# CC-S09-V00-PSU-3V3.net
KiCad netlist of a schematic drawn in Altium Designer
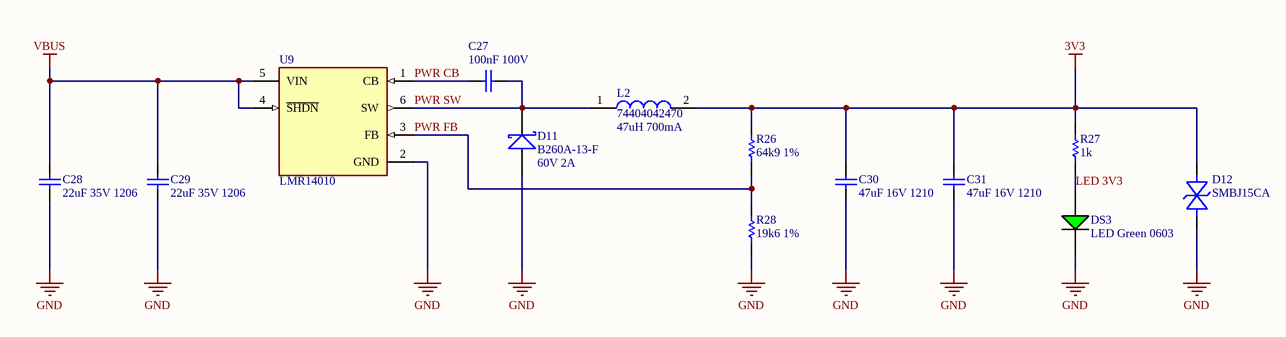
[diagram p0: CC-S09-V00-PSU-3V3.SchDoc]

(export (version "E")
  (design (tool "Eeschema 10.0.6"))
  (components
    (comp (ref "C27")
      (value "100nF 100V")
      (footprint "Cap_Ceramic_0603")
      (description "Capacitor, Ceramic, SMD, 100nF, 100V, 5%, X7R, 0603")
      (libsource (lib "StandardCapacitors") (part "100nF 100V 5% X7R 0603"))
    )
    (comp (ref "C28")
      (value "22uF 35V 1206")
      (footprint "Cap_Ceramic_1206")
      (description "Capacitor, Ceramic, SMD, 22uF, 35V, 10%, X7R, 1206")
      (libsource (lib "StandardCapacitors") (part "22uF 35V 10% X7R 1206"))
    )
    (comp (ref "C29")
      (value "22uF 35V 1206")
      (footprint "Cap_Ceramic_1206")
      (description "Capacitor, Ceramic, SMD, 22uF, 35V, 10%, X7R, 1206")
      (libsource (lib "StandardCapacitors") (part "22uF 35V 10% X7R 1206"))
    )
    (comp (ref "C30")
      (value "47uF 16V 1210")
      (footprint "Cap_Ceramic_1210")
      (description "Capacitor, Ceramic, SMD, 47uF, 16V, 5%, X7R, 1210")
      (libsource (lib "StandardCapacitors") (part "47uF 16V 10% X7R 1210"))
    )
    (comp (ref "C31")
      (value "47uF 16V 1210")
      (footprint "Cap_Ceramic_1210")
      (description "Capacitor, Ceramic, SMD, 47uF, 16V, 5%, X7R, 1210")
      (libsource (lib "StandardCapacitors") (part "47uF 16V 10% X7R 1210"))
    )
    (comp (ref "D11")
      (value "B260A-13-F")
      (footprint "SMA")
      (description "Diode, Schottky Barrier Rectifier, 60 V, 2 A, B260A-13-F")
      (libsource (lib "QUTMS_DiodeLibrary") (part "B260A-13-F"))
    )
    (comp (ref "D12")
      (value "SMBJ15CA")
      (footprint "SMB")
      (description "Diode, SMD, TVS Diode, 15V 24.4V, DO214AA/SMB")
      (libsource (lib "QUTMS_DiodeLibrary") (part "SMBJ15CA"))
    )
    (comp (ref "DS3")
      (value "LED Green 0603")
      (footprint "LED GREEN 0603")
      (libsource (lib "QUTMS_LEDLibrary") (part "LED Green 0603"))
    )
    (comp (ref "L2")
      (value "74404042470")
      (footprint "INDUCTOR_4X3MM_1.8MM")
      (description "47µH Semi-Shielded Wirewound Inductor 600mA 620mOhm Nonstandard")
      (libsource (lib "QUTMS_InductorLibrary") (part "74404042470"))
    )
    (comp (ref "R26")
      (value "64k9 1%")
      (footprint "Res_ThinFilm_0603")
      (description "Resistor, SMD, 64k9, 0.1W, 5%, 0603")
      (libsource (lib "StandardResistors") (part "64k9 1% 0603"))
    )
    (comp (ref "R27")
      (value "1k")
      (footprint "Res_ThinFilm_0603")
      (description "Resistor, SMD, 1k, 0.1W, 5%, 0603")
      (libsource (lib "StandardResistors") (part "1k 5% 0603"))
    )
    (comp (ref "R28")
      (value "19k6 1%")
      (footprint "Res_ThinFilm_0603")
      (description "Resistor, SMD, 19k6, 0.1W, 5%, 0603")
      (libsource (lib "StandardResistors") (part "19k6 1% 0603"))
    )
    (comp (ref "U9")
      (value "LMR14010")
      (footprint "LMR14010")
      (libsource (lib "QUTMS_PowerSupplyLibrary") (part "LMR14010"))
    )
  )
  (nets
    (net (code "1") (name "/LED 3V3") (class "Default")
      (node (ref "DS3") (pin "1") (pinfunction "A_1") (pintype "passive"))
      (node (ref "R27") (pin "1") (pinfunction "1_1") (pintype "passive"))
    )
    (net (code "2") (name "/PWR CB") (class "Default")
      (node (ref "C27") (pin "1") (pinfunction "1_1") (pintype "passive"))
      (node (ref "U9") (pin "1") (pinfunction "CB_1") (pintype "input"))
    )
    (net (code "3") (name "/PWR FB") (class "Default")
      (node (ref "R26") (pin "1") (pinfunction "1_1") (pintype "passive"))
      (node (ref "R28") (pin "2") (pinfunction "2_2") (pintype "passive"))
      (node (ref "U9") (pin "3") (pinfunction "FB_3") (pintype "input"))
    )
    (net (code "4") (name "/PWR SW") (class "Default")
      (node (ref "C27") (pin "2") (pinfunction "2_2") (pintype "passive"))
      (node (ref "D11") (pin "K") (pinfunction "K_K") (pintype "passive"))
      (node (ref "L2") (pin "1") (pinfunction "1_1") (pintype "passive"))
      (node (ref "U9") (pin "6") (pinfunction "SW_6") (pintype "output"))
    )
    (net (code "5") (name "3V3") (class "Default")
      (node (ref "C30") (pin "2") (pinfunction "2_2") (pintype "passive"))
      (node (ref "C31") (pin "2") (pinfunction "2_2") (pintype "passive"))
      (node (ref "D12") (pin "K") (pinfunction "Cathode_K") (pintype "passive"))
      (node (ref "L2") (pin "2") (pinfunction "2_2") (pintype "passive"))
      (node (ref "R26") (pin "2") (pinfunction "2_2") (pintype "passive"))
      (node (ref "R27") (pin "2") (pinfunction "2_2") (pintype "passive"))
    )
    (net (code "6") (name "GND") (class "Default")
      (node (ref "C28") (pin "1") (pinfunction "1_1") (pintype "passive"))
      (node (ref "C29") (pin "1") (pinfunction "1_1") (pintype "passive"))
      (node (ref "C30") (pin "1") (pinfunction "1_1") (pintype "passive"))
      (node (ref "C31") (pin "1") (pinfunction "1_1") (pintype "passive"))
      (node (ref "D11") (pin "A") (pinfunction "A_A") (pintype "passive"))
      (node (ref "D12") (pin "A") (pinfunction "Anode_A") (pintype "passive"))
      (node (ref "DS3") (pin "2") (pinfunction "C_2") (pintype "passive"))
      (node (ref "R28") (pin "1") (pinfunction "1_1") (pintype "passive"))
      (node (ref "U9") (pin "2") (pinfunction "GND_2") (pintype "power_in"))
    )
    (net (code "7") (name "VBUS") (class "Default")
      (node (ref "C28") (pin "2") (pinfunction "2_2") (pintype "passive"))
      (node (ref "C29") (pin "2") (pinfunction "2_2") (pintype "passive"))
      (node (ref "U9") (pin "4") (pinfunction "~{SHDN}_4") (pintype "input"))
      (node (ref "U9") (pin "5") (pinfunction "VIN_5") (pintype "power_in"))
    )
  )
)
